# Power.net
KiCad netlist of a schematic drawn in Altium Designer
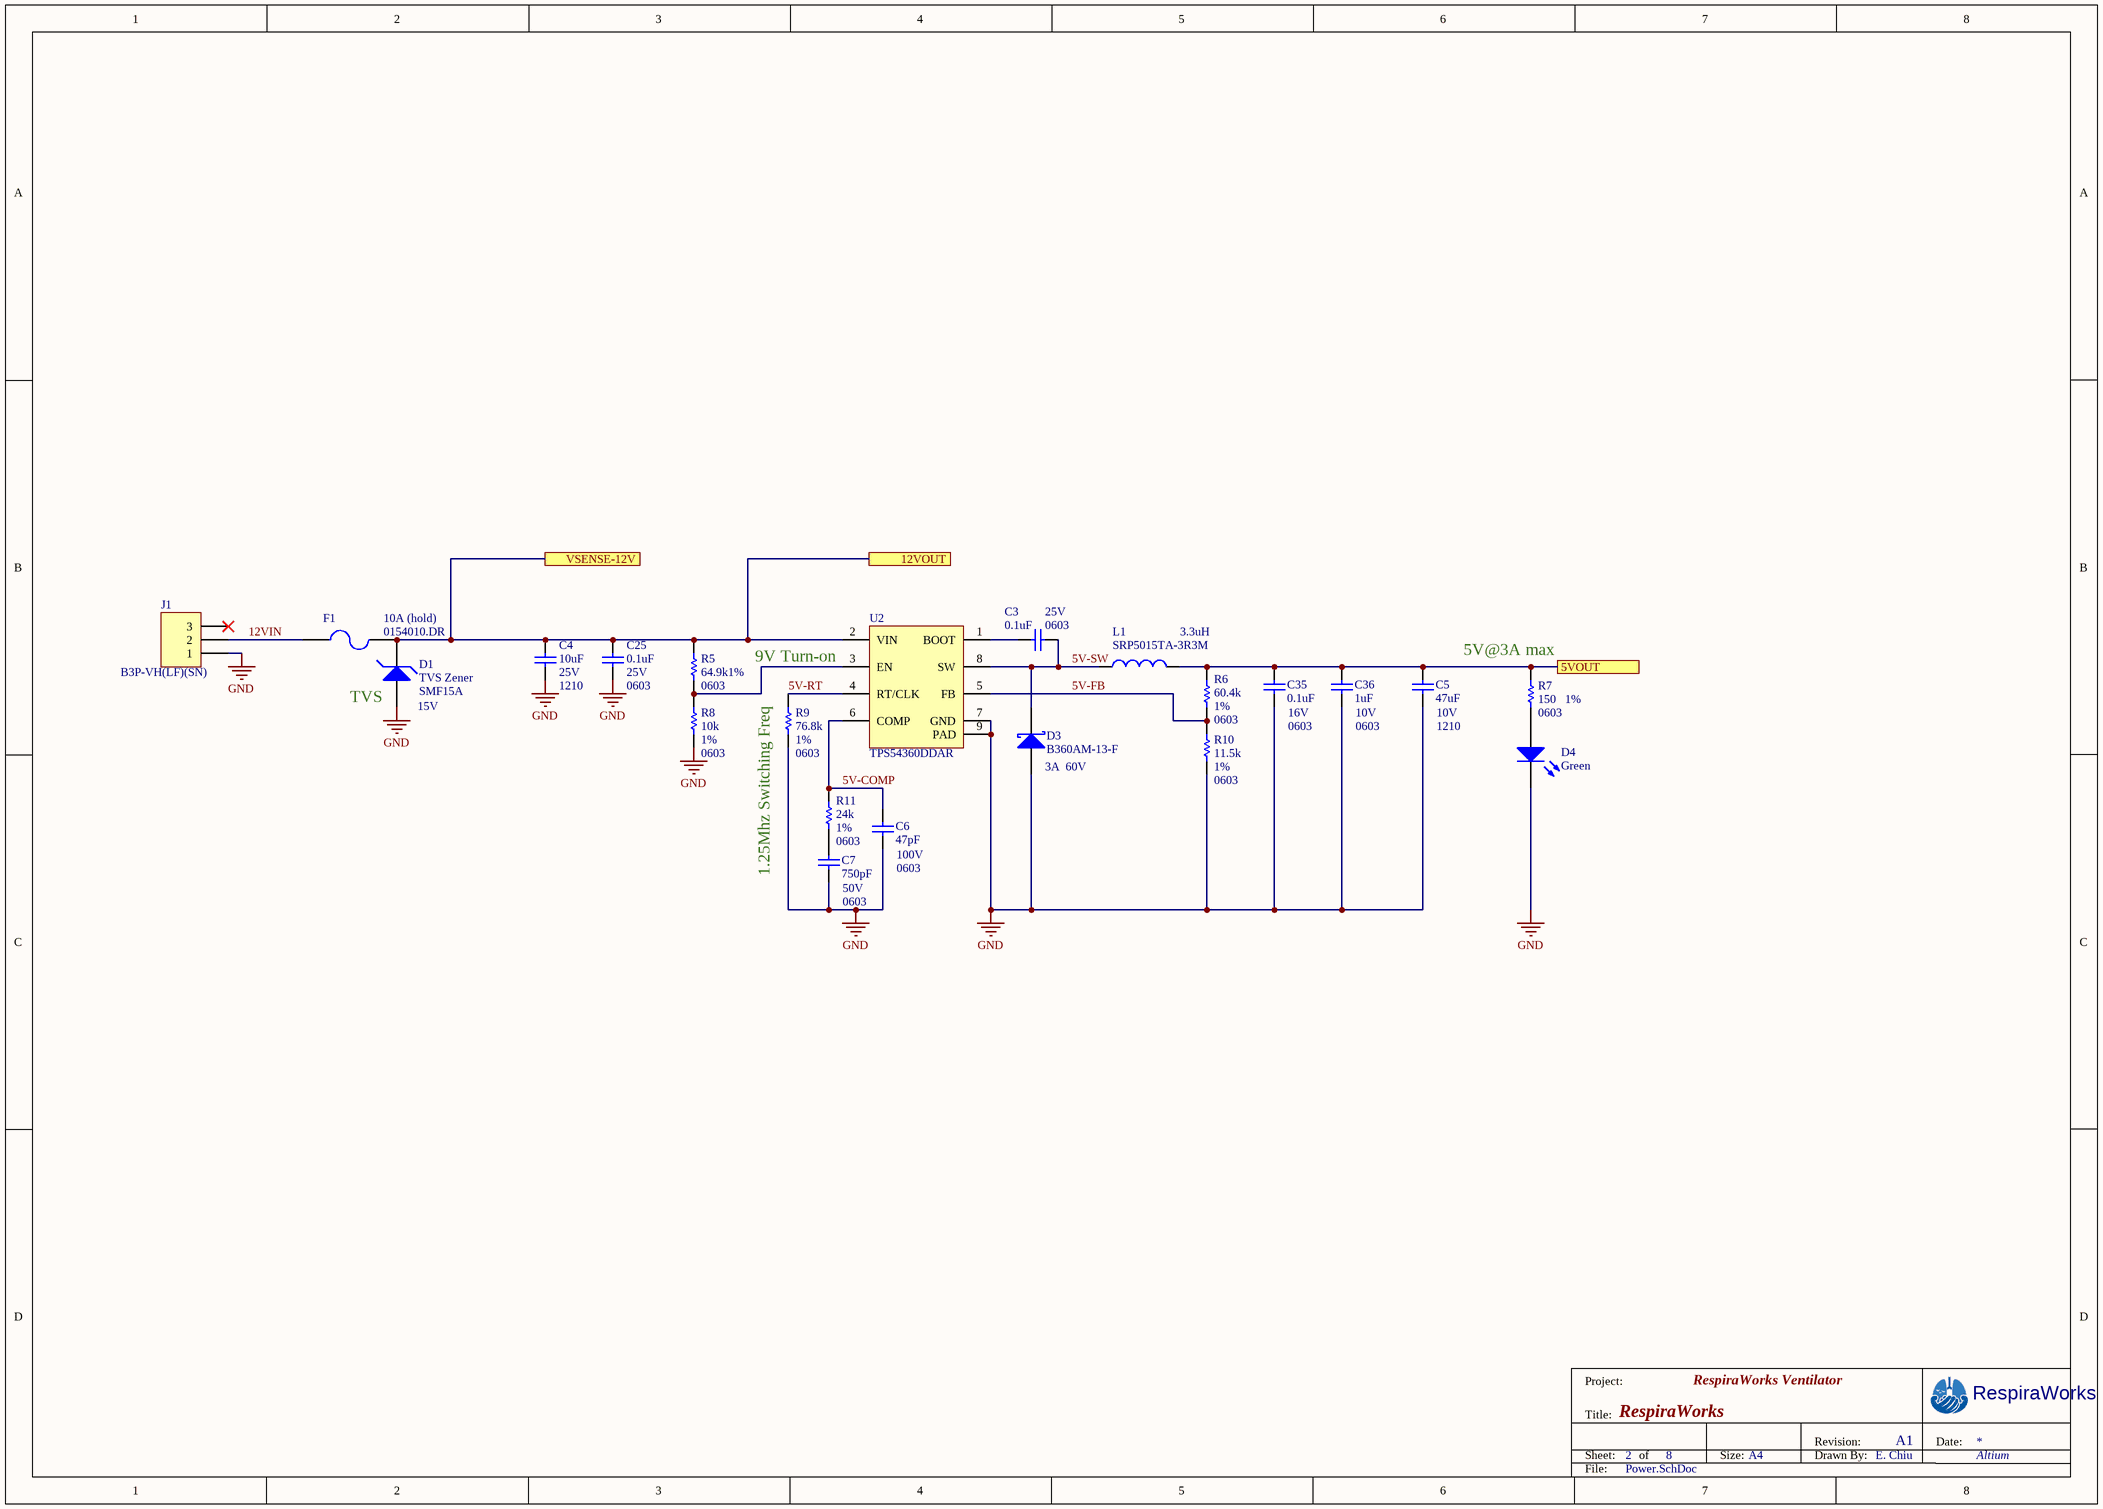
[diagram p0: Power.SchDoc]

(export (version "E")
  (design (tool "Eeschema 10.0.6"))
  (components
    (comp (ref "C3")
      (value "0.1uF")
      (footprint "CAP0603")
      (description "Cap 0603")
      (fields
        (field (name "MANUFACTURER") "Yageo")
        (field (name "VOLTAGE") "25V")
        (field (name "PCB PACKAGE") "0603")
        (field (name "Comment") "CAP 0603")
      )
      (libsource (lib "generic") (part "CAP 0603"))
    )
    (comp (ref "C4")
      (value "10uF")
      (footprint "CAP1210")
      (description "Cap 1210")
      (fields
        (field (name "MANUFACTURER") "Murata")
        (field (name "VOLTAGE") "25V")
        (field (name "PCB PACKAGE") "1210")
        (field (name "Comment") "CAP 1210")
      )
      (libsource (lib "generic") (part "CAP 1210"))
    )
    (comp (ref "C5")
      (value "47uF")
      (footprint "CAP1210")
      (description "Cap 1210")
      (fields
        (field (name "MANUFACTURER") "Murata")
        (field (name "VOLTAGE") "10V")
        (field (name "PCB PACKAGE") "1210")
        (field (name "Comment") "CAP 1210")
      )
      (libsource (lib "generic") (part "CAP 1210"))
    )
    (comp (ref "C6")
      (value "47pF")
      (footprint "CAP0603")
      (description "Cap 0603")
      (fields
        (field (name "MANUFACTURER") "Kemet")
        (field (name "VOLTAGE") "100V")
        (field (name "PCB PACKAGE") "0603")
        (field (name "Comment") "CAP 0603")
      )
      (libsource (lib "generic") (part "CAP 0603"))
    )
    (comp (ref "C7")
      (value "750pF")
      (footprint "CAP0603")
      (description "Cap 0603")
      (fields
        (field (name "MANUFACTURER") "Samsung")
        (field (name "VOLTAGE") "50V")
        (field (name "PCB PACKAGE") "0603")
        (field (name "Comment") "CAP 0603")
      )
      (libsource (lib "generic") (part "CAP 0603"))
    )
    (comp (ref "C25")
      (value "0.1uF")
      (footprint "CAP0603")
      (description "Cap 0603")
      (fields
        (field (name "MANUFACTURER") "Yageo")
        (field (name "VOLTAGE") "25V")
        (field (name "PCB PACKAGE") "0603")
        (field (name "Comment") "CAP 0603")
      )
      (libsource (lib "generic") (part "CAP 0603"))
    )
    (comp (ref "C35")
      (value "0.1uF")
      (footprint "CAP0603")
      (description "Cap 0603")
      (fields
        (field (name "MANUFACTURER") "Yageo")
        (field (name "VOLTAGE") "16V")
        (field (name "PCB PACKAGE") "0603")
        (field (name "Comment") "CAP 0603")
      )
      (libsource (lib "generic") (part "CAP 0603"))
    )
    (comp (ref "C36")
      (value "1uF")
      (footprint "CAP0603")
      (description "Cap 0603")
      (fields
        (field (name "MANUFACTURER") "Yageo")
        (field (name "VOLTAGE") "10V")
        (field (name "PCB PACKAGE") "0603")
        (field (name "Comment") "CAP 0603")
      )
      (libsource (lib "generic") (part "CAP 0603"))
    )
    (comp (ref "D1")
      (value "TVS Zener")
      (footprint "SOD-123F")
      (description "TVS Diode, Zener, 15V Standoff, 24V Clamp, 8.2A")
      (fields
        (field (name "MANUFACTURER") "Littelfuse")
        (field (name "VR") "15V")
        (field (name "MANUFACTURER P/N") "SMF15A")
      )
      (libsource (lib "littelfuse") (part "SMF15A"))
    )
    (comp (ref "D3")
      (value "*")
      (footprint "DO-214AC")
      (description "DIODE SCHOTTKY 60V 3A SMA")
      (fields
        (field (name "MANUFACTURER") "Diodes Inc.")
        (field (name "REVERSE VOLTAGE") "60V")
        (field (name "I(MAX)") "3A")
        (field (name "MANUFACTURER P/N") "B360AM-13-F")
      )
      (libsource (lib "diodes-inc") (part "B360AM-13-F"))
    )
    (comp (ref "D4")
      (value "Green")
      (footprint "LED0603")
      (description "LED 0603")
      (fields (field (name "MANUFACTURER") "Lite-On"))
      (libsource (lib "generic") (part "LED 0603"))
    )
    (comp (ref "F1")
      (value "10A (hold)")
      (footprint "0154")
      (description "Fast Blow Nano Fuse in Holder, 10A, 125V")
      (fields
        (field (name "MANUFACTURER") "Littelfuse")
        (field (name "MANUFACTURER P/N") "0154010.DR")
        (field (name "Comment") "Fast Blow")
      )
      (libsource (lib "littelfuse") (part "0154010"))
    )
    (comp (ref "J1")
      (value "B3P-VH(LF)(SN)")
      (footprint "B3P-VH(LF)(SN)")
      (description "JST-VH HEADER VERT 3POS 3.96MM")
      (fields (field (name "MANUFACTURER") "JST") (field (name "MANUFACTURER P/N") "B3P-VH(LF)(SN)"))
      (libsource (lib "JST") (part "B3P-VH(LF)(SN)"))
    )
    (comp (ref "L1")
      (value "3.3uH")
      (footprint "SRP5015")
      (description "Inductor, 501 Series, Shielded 2.2uH, 4A")
      (fields
        (field (name "MANUFACTURER") "Bourns")
        (field (name "MANUFACTURER P/N") "SRP5015TA-3R3M")
        (field (name "Comment") "SRP5015TA-3R3M")
      )
      (libsource (lib "bourns") (part "SRP5015TA-3R3M"))
    )
    (comp (ref "R5")
      (value "64.9k")
      (footprint "RES0603")
      (description "Res 0603")
      (fields
        (field (name "MANUFACTURER") "Yageo")
        (field (name "PCB PACKAGE") "0603")
        (field (name "TOLERANCE") "1%")
        (field (name "Comment") "RES 0603")
      )
      (libsource (lib "generic") (part "RES 0603"))
    )
    (comp (ref "R6")
      (value "60.4k")
      (footprint "RES0603")
      (description "Res 0603")
      (fields
        (field (name "MANUFACTURER") "Yageo")
        (field (name "PCB PACKAGE") "0603")
        (field (name "TOLERANCE") "1%")
        (field (name "Comment") "RES 0603")
      )
      (libsource (lib "generic") (part "RES 0603"))
    )
    (comp (ref "R7")
      (value "150")
      (footprint "RES0603")
      (description "Res 0603")
      (fields
        (field (name "MANUFACTURER") "Panasonic")
        (field (name "PCB PACKAGE") "0603")
        (field (name "TOLERANCE") "1%")
        (field (name "Comment") "RES 0603")
      )
      (libsource (lib "generic") (part "RES 0603"))
    )
    (comp (ref "R8")
      (value "10k")
      (footprint "RES0603")
      (description "Res 0603")
      (fields
        (field (name "MANUFACTURER") "Panasonic")
        (field (name "PCB PACKAGE") "0603")
        (field (name "TOLERANCE") "1%")
        (field (name "Comment") "RES 0603")
      )
      (libsource (lib "generic") (part "RES 0603"))
    )
    (comp (ref "R9")
      (value "76.8k")
      (footprint "RES0603")
      (description "Res 0603")
      (fields
        (field (name "MANUFACTURER") "Yageo")
        (field (name "PCB PACKAGE") "0603")
        (field (name "TOLERANCE") "1%")
        (field (name "Comment") "RES 0603")
      )
      (libsource (lib "generic") (part "RES 0603"))
    )
    (comp (ref "R10")
      (value "11.5k")
      (footprint "RES0603")
      (description "Res 0603")
      (fields
        (field (name "MANUFACTURER") "Yageo")
        (field (name "PCB PACKAGE") "0603")
        (field (name "TOLERANCE") "1%")
        (field (name "Comment") "RES 0603")
      )
      (libsource (lib "generic") (part "RES 0603"))
    )
    (comp (ref "R11")
      (value "24k")
      (footprint "RES0603")
      (description "Res 0603")
      (fields
        (field (name "MANUFACTURER") "Panasonic")
        (field (name "PCB PACKAGE") "0603")
        (field (name "TOLERANCE") "1%")
        (field (name "Comment") "RES 0603")
      )
      (libsource (lib "generic") (part "RES 0603"))
    )
    (comp (ref "U2")
      (value "TPS54360")
      (footprint "DDA")
      (description "DC-DC Buck, 60V Input, 3.5A Int Sw, Ultra Low Quiescent Power")
      (fields
        (field (name "MANUFACTURER") "Texas Instruments")
        (field (name "MANUFACTURER P/N") "TPS54360DDAR")
      )
      (libsource (lib "ti") (part "TPS54360"))
    )
  )
  (nets
    (net (code "1") (name "/5V-COMP") (class "Default")
      (node (ref "C6") (pin "2") (pinfunction "2_2") (pintype "passive"))
      (node (ref "R11") (pin "2") (pinfunction "2_2") (pintype "passive"))
      (node (ref "U2") (pin "6") (pinfunction "COMP_6") (pintype "passive"))
    )
    (net (code "2") (name "/5V-FB") (class "Default")
      (node (ref "R10") (pin "2") (pinfunction "2_2") (pintype "passive"))
      (node (ref "R6") (pin "1") (pinfunction "1_1") (pintype "passive"))
      (node (ref "U2") (pin "5") (pinfunction "FB_5") (pintype "passive"))
    )
    (net (code "3") (name "/5V-RT") (class "Default")
      (node (ref "R9") (pin "2") (pinfunction "2_2") (pintype "passive"))
      (node (ref "U2") (pin "4") (pinfunction "RT/CLK_4") (pintype "passive"))
    )
    (net (code "4") (name "/5V-SW") (class "Default")
      (node (ref "C3") (pin "2") (pinfunction "2_2") (pintype "passive"))
      (node (ref "D3") (pin "K") (pinfunction "K_K") (pintype "passive"))
      (node (ref "L1") (pin "1") (pinfunction "1_1") (pintype "passive"))
      (node (ref "U2") (pin "8") (pinfunction "SW_8") (pintype "passive"))
    )
    (net (code "5") (name "/5VOUT") (class "Default")
      (node (ref "C35") (pin "1") (pinfunction "1_1") (pintype "passive"))
      (node (ref "C36") (pin "1") (pinfunction "1_1") (pintype "passive"))
      (node (ref "C5") (pin "2") (pinfunction "2_2") (pintype "passive"))
      (node (ref "L1") (pin "2") (pinfunction "2_2") (pintype "passive"))
      (node (ref "R6") (pin "2") (pinfunction "2_2") (pintype "passive"))
      (node (ref "R7") (pin "2") (pinfunction "2_2") (pintype "passive"))
    )
    (net (code "6") (name "/12VIN") (class "Default")
      (node (ref "F1") (pin "1") (pinfunction "1_1") (pintype "passive"))
      (node (ref "J1") (pin "2") (pinfunction "2_2") (pintype "passive"))
    )
    (net (code "7") (name "/12VOUT") (class "Default")
      (node (ref "C25") (pin "1") (pinfunction "1_1") (pintype "passive"))
      (node (ref "C4") (pin "2") (pinfunction "2_2") (pintype "passive"))
      (node (ref "D1") (pin "K") (pinfunction "K_K") (pintype "passive"))
      (node (ref "F1") (pin "2") (pinfunction "2_2") (pintype "passive"))
      (node (ref "R5") (pin "2") (pinfunction "2_2") (pintype "passive"))
      (node (ref "U2") (pin "2") (pinfunction "VIN_2") (pintype "passive"))
    )
    (net (code "8") (name "GND") (class "Default")
      (node (ref "C25") (pin "2") (pinfunction "2_2") (pintype "passive"))
      (node (ref "C35") (pin "2") (pinfunction "2_2") (pintype "passive"))
      (node (ref "C36") (pin "2") (pinfunction "2_2") (pintype "passive"))
      (node (ref "C4") (pin "1") (pinfunction "1_1") (pintype "passive"))
      (node (ref "C5") (pin "1") (pinfunction "1_1") (pintype "passive"))
      (node (ref "C6") (pin "1") (pinfunction "1_1") (pintype "passive"))
      (node (ref "C7") (pin "1") (pinfunction "1_1") (pintype "passive"))
      (node (ref "D1") (pin "A") (pinfunction "A_A") (pintype "passive"))
      (node (ref "D3") (pin "A") (pinfunction "A_A") (pintype "passive"))
      (node (ref "D4") (pin "K") (pinfunction "K_K") (pintype "passive"))
      (node (ref "J1") (pin "1") (pinfunction "1_1") (pintype "passive"))
      (node (ref "R10") (pin "1") (pinfunction "1_1") (pintype "passive"))
      (node (ref "R8") (pin "1") (pinfunction "1_1") (pintype "passive"))
      (node (ref "R9") (pin "1") (pinfunction "1_1") (pintype "passive"))
      (node (ref "U2") (pin "7") (pinfunction "GND_7") (pintype "passive"))
      (node (ref "U2") (pin "9") (pinfunction "PAD_9") (pintype "passive"))
    )
    (net (code "9") (name "Net-(C7-Pad2)") (class "Default")
      (node (ref "C7") (pin "2") (pinfunction "2_2") (pintype "passive"))
      (node (ref "R11") (pin "1") (pinfunction "1_1") (pintype "passive"))
    )
    (net (code "10") (name "Net-(D4-PadA)") (class "Default")
      (node (ref "D4") (pin "A") (pinfunction "A_A") (pintype "passive"))
      (node (ref "R7") (pin "1") (pinfunction "1_1") (pintype "passive"))
    )
    (net (code "11") (name "Net-(U2-BOOT)") (class "Default")
      (node (ref "C3") (pin "1") (pinfunction "1_1") (pintype "passive"))
      (node (ref "U2") (pin "1") (pinfunction "BOOT_1") (pintype "passive"))
    )
    (net (code "12") (name "Net-(U2-EN)") (class "Default")
      (node (ref "R5") (pin "1") (pinfunction "1_1") (pintype "passive"))
      (node (ref "R8") (pin "2") (pinfunction "2_2") (pintype "passive"))
      (node (ref "U2") (pin "3") (pinfunction "EN_3") (pintype "passive"))
    )
    (net (code "13") (name "unconnected-(J1-Pad3)") (class "Default")
      (node (ref "J1") (pin "3") (pinfunction "3_3") (pintype "passive+no_connect"))
    )
  )
)
